# TaggerBits0_1.net
KiCad netlist of a schematic drawn in EAGLE
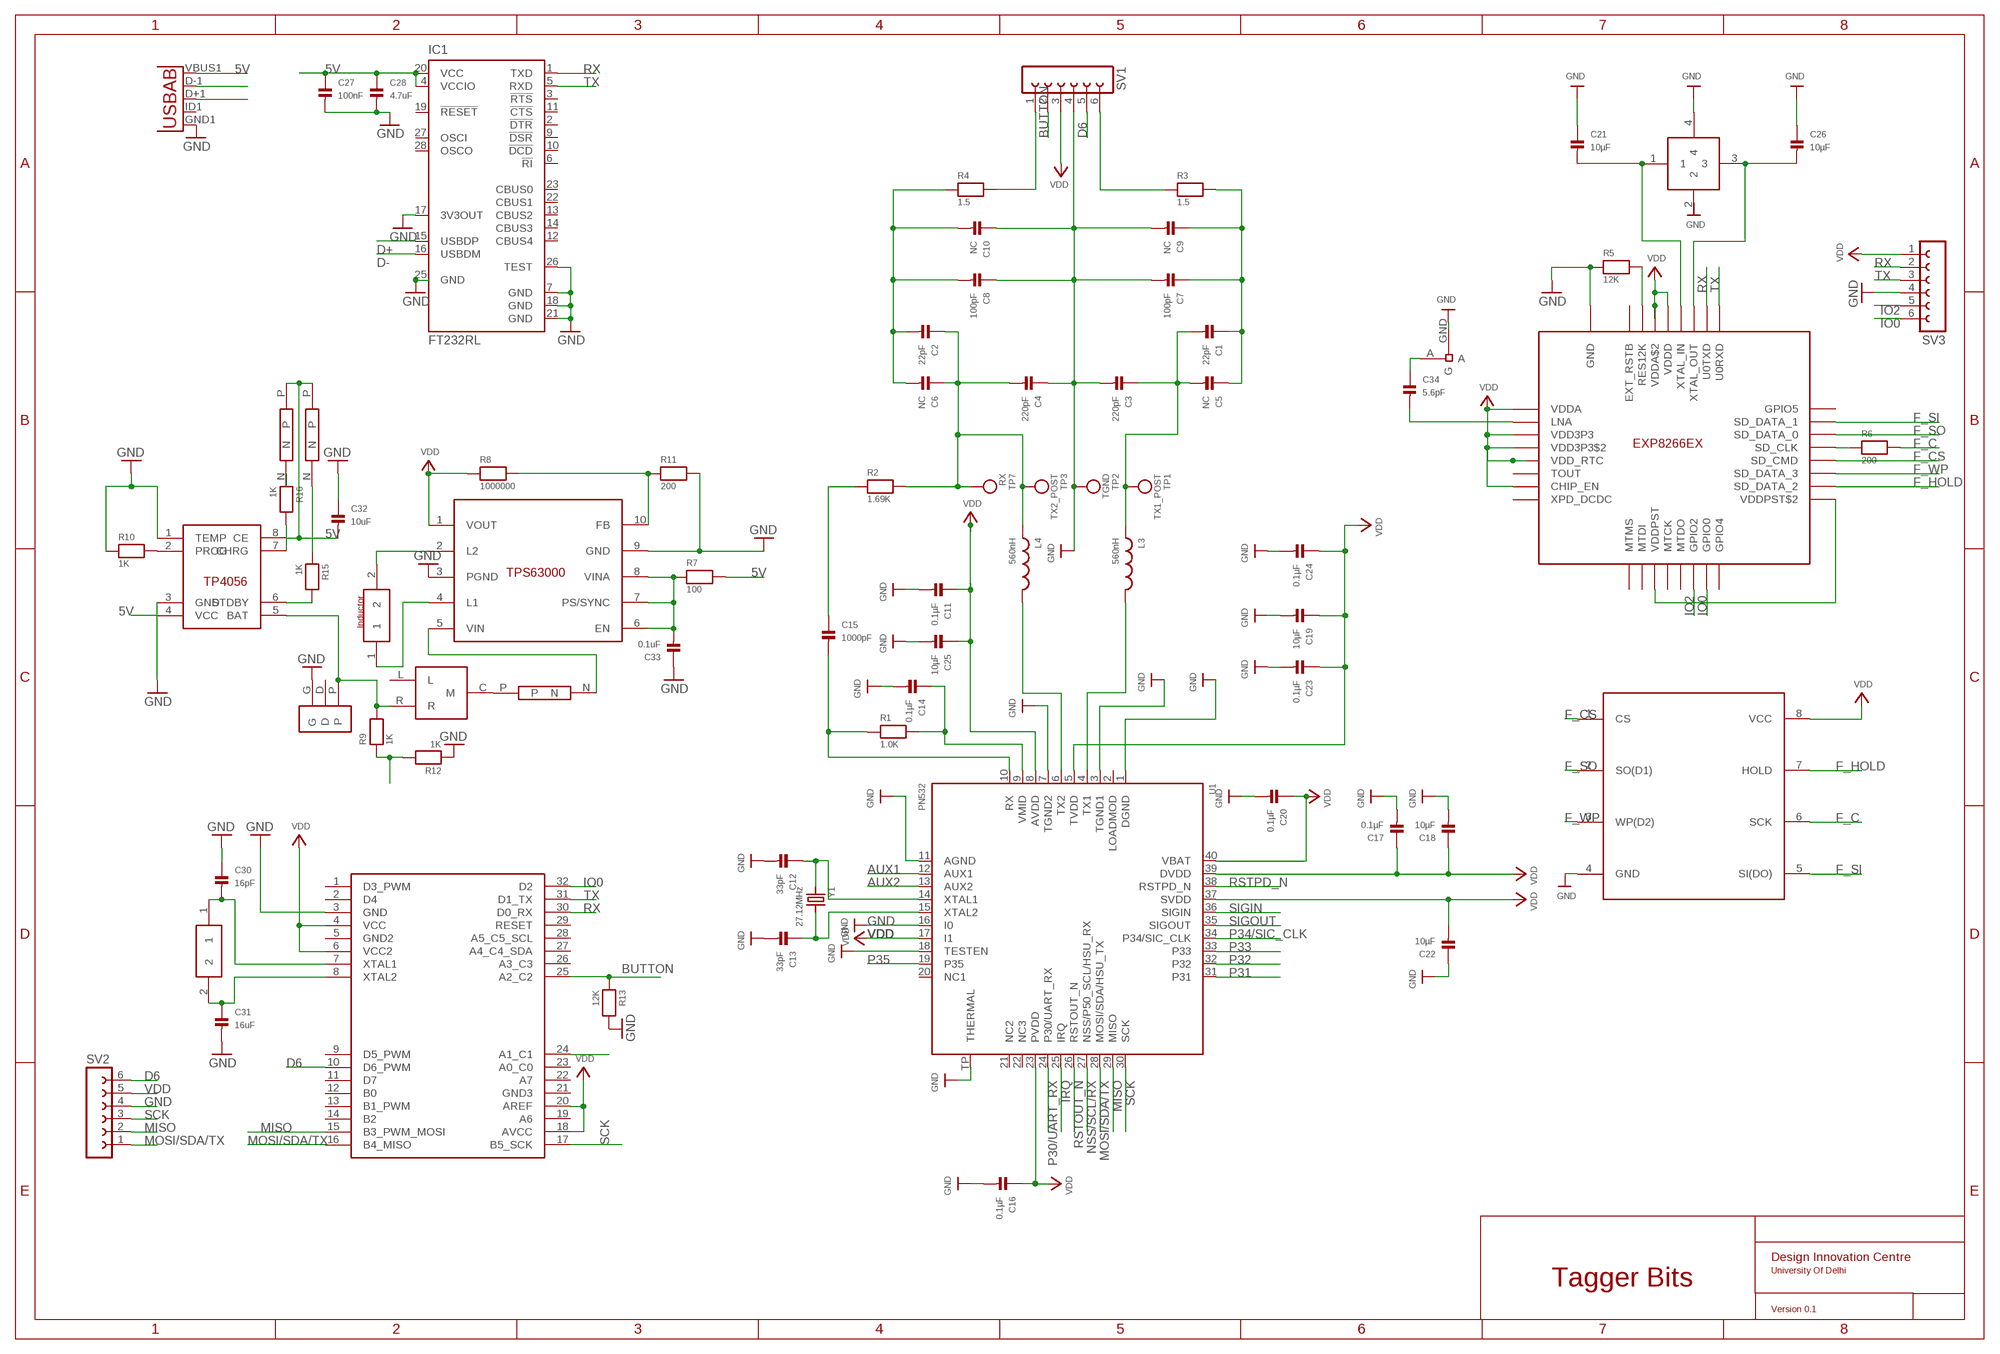
[diagram p0: schematic, sheet 1]

(export (version "E")
  (design (tool "Eeschema 10.0.6"))
  (components
    (comp (ref "C1")
      (value "22pF")
      (footprint "eagle-import:0805")
      (libsource (lib "eagle-import") (part "CAP_CERAMIC0805"))
    )
    (comp (ref "C2")
      (value "22pF")
      (footprint "eagle-import:0805")
      (libsource (lib "eagle-import") (part "CAP_CERAMIC0805"))
    )
    (comp (ref "C3")
      (value "220pF")
      (footprint "eagle-import:0805")
      (libsource (lib "eagle-import") (part "CAP_CERAMIC0805"))
    )
    (comp (ref "C4")
      (value "220pF")
      (footprint "eagle-import:0805")
      (libsource (lib "eagle-import") (part "CAP_CERAMIC0805"))
    )
    (comp (ref "C5")
      (value "NC")
      (footprint "eagle-import:0805")
      (libsource (lib "eagle-import") (part "CAP_CERAMIC0805"))
    )
    (comp (ref "C6")
      (value "NC")
      (footprint "eagle-import:0805")
      (libsource (lib "eagle-import") (part "CAP_CERAMIC0805"))
    )
    (comp (ref "C7")
      (value "100pF")
      (footprint "eagle-import:0805")
      (libsource (lib "eagle-import") (part "CAP_CERAMIC0805"))
    )
    (comp (ref "C8")
      (value "100pF")
      (footprint "eagle-import:0805")
      (libsource (lib "eagle-import") (part "CAP_CERAMIC0805"))
    )
    (comp (ref "C9")
      (value "NC")
      (footprint "eagle-import:0805")
      (libsource (lib "eagle-import") (part "CAP_CERAMIC0805"))
    )
    (comp (ref "C10")
      (value "NC")
      (footprint "eagle-import:0805")
      (libsource (lib "eagle-import") (part "CAP_CERAMIC0805"))
    )
    (comp (ref "C11")
      (value "0.1µF")
      (footprint "eagle-import:0805")
      (libsource (lib "eagle-import") (part "CAP_CERAMIC0805"))
    )
    (comp (ref "C12")
      (value "33pF")
      (footprint "eagle-import:0805")
      (libsource (lib "eagle-import") (part "CAP_CERAMIC0805"))
    )
    (comp (ref "C13")
      (value "33pF")
      (footprint "eagle-import:0805")
      (libsource (lib "eagle-import") (part "CAP_CERAMIC0805"))
    )
    (comp (ref "C14")
      (value "0.1µF")
      (footprint "eagle-import:0805")
      (libsource (lib "eagle-import") (part "CAP_CERAMIC0805"))
    )
    (comp (ref "C15")
      (value "1000pF")
      (footprint "eagle-import:0805")
      (libsource (lib "eagle-import") (part "CAP_CERAMIC0805"))
    )
    (comp (ref "C16")
      (value "0.1µF")
      (footprint "eagle-import:0805")
      (libsource (lib "eagle-import") (part "CAP_CERAMIC0805"))
    )
    (comp (ref "C17")
      (value "0.1µF")
      (footprint "eagle-import:0805")
      (libsource (lib "eagle-import") (part "CAP_CERAMIC0805"))
    )
    (comp (ref "C18")
      (value "10µF")
      (footprint "eagle-import:0805")
      (libsource (lib "eagle-import") (part "CAP_CERAMIC0805"))
    )
    (comp (ref "C19")
      (value "10µF")
      (footprint "eagle-import:0805")
      (libsource (lib "eagle-import") (part "CAP_CERAMIC0805"))
    )
    (comp (ref "C20")
      (value "0.1µF")
      (footprint "eagle-import:0805")
      (libsource (lib "eagle-import") (part "CAP_CERAMIC0805"))
    )
    (comp (ref "C21")
      (value "10µF")
      (footprint "eagle-import:0805")
      (libsource (lib "eagle-import") (part "CAP_CERAMIC0805"))
    )
    (comp (ref "C22")
      (value "10µF")
      (footprint "eagle-import:0805")
      (libsource (lib "eagle-import") (part "CAP_CERAMIC0805"))
    )
    (comp (ref "C23")
      (value "0.1µF")
      (footprint "eagle-import:0805")
      (libsource (lib "eagle-import") (part "CAP_CERAMIC0805"))
    )
    (comp (ref "C24")
      (value "0.1µF")
      (footprint "eagle-import:0805")
      (libsource (lib "eagle-import") (part "CAP_CERAMIC0805"))
    )
    (comp (ref "C25")
      (value "10µF")
      (footprint "eagle-import:0805")
      (libsource (lib "eagle-import") (part "CAP_CERAMIC0805"))
    )
    (comp (ref "C26")
      (value "10µF")
      (footprint "eagle-import:0805")
      (libsource (lib "eagle-import") (part "CAP_CERAMIC0805"))
    )
    (comp (ref "C27")
      (value "100nF")
      (footprint "eagle-import:0805")
      (libsource (lib "eagle-import") (part "CAP_CERAMIC0805"))
    )
    (comp (ref "C28")
      (value "4.7uF")
      (footprint "eagle-import:0805")
      (libsource (lib "eagle-import") (part "CAP_CERAMIC0805"))
    )
    (comp (ref "C30")
      (value "16pF")
      (footprint "eagle-import:0805")
      (libsource (lib "eagle-import") (part "CAP_CERAMIC0805"))
    )
    (comp (ref "C31")
      (value "16uF")
      (footprint "eagle-import:0805")
      (libsource (lib "eagle-import") (part "CAP_CERAMIC0805"))
    )
    (comp (ref "C32")
      (value "10uF")
      (footprint "eagle-import:0805")
      (libsource (lib "eagle-import") (part "CAP_CERAMIC0805"))
    )
    (comp (ref "C33")
      (value "0.1uF")
      (footprint "eagle-import:0805")
      (libsource (lib "eagle-import") (part "CAP_CERAMIC0805"))
    )
    (comp (ref "C34")
      (value "5.6pF")
      (footprint "eagle-import:0805")
      (libsource (lib "eagle-import") (part "CAP_CERAMIC0805"))
    )
    (comp (ref "GREEN")
      (value "LED(805)")
      (footprint "eagle-import:LED(805)")
      (libsource (lib "eagle-import") (part "LED(805)"))
    )
    (comp (ref "IC1")
      (value "FT232RL")
      (footprint "eagle-import:SSOP28")
      (libsource (lib "eagle-import") (part "FT232RL"))
    )
    (comp (ref "L3")
      (value "560nH")
      (footprint "eagle-import:0805")
      (libsource (lib "eagle-import") (part "INDUCTOR0805"))
    )
    (comp (ref "L4")
      (value "560nH")
      (footprint "eagle-import:0805")
      (libsource (lib "eagle-import") (part "INDUCTOR0805"))
    )
    (comp (ref "LED")
      (value "LED(805)")
      (footprint "eagle-import:LED(805)")
      (libsource (lib "eagle-import") (part "LED(805)"))
    )
    (comp (ref "R1")
      (value "1.0K")
      (footprint "eagle-import:0805")
      (libsource (lib "eagle-import") (part "RESISTOR0805"))
    )
    (comp (ref "R2")
      (value "1.69K")
      (footprint "eagle-import:0805")
      (libsource (lib "eagle-import") (part "RESISTOR0805"))
    )
    (comp (ref "R3")
      (value "1.5")
      (footprint "eagle-import:0805")
      (libsource (lib "eagle-import") (part "RESISTOR0805"))
    )
    (comp (ref "R4")
      (value "1.5")
      (footprint "eagle-import:0805")
      (libsource (lib "eagle-import") (part "RESISTOR0805"))
    )
    (comp (ref "R5")
      (value "12K")
      (footprint "eagle-import:0805")
      (libsource (lib "eagle-import") (part "RESISTOR0805"))
    )
    (comp (ref "R6")
      (value "200")
      (footprint "eagle-import:0805")
      (libsource (lib "eagle-import") (part "RESISTOR0805"))
    )
    (comp (ref "R7")
      (value "100")
      (footprint "eagle-import:0805")
      (libsource (lib "eagle-import") (part "RESISTOR0805"))
    )
    (comp (ref "R8")
      (value "1000000")
      (footprint "eagle-import:0805")
      (libsource (lib "eagle-import") (part "RESISTOR0805"))
    )
    (comp (ref "R9")
      (value "1K")
      (footprint "eagle-import:0805")
      (libsource (lib "eagle-import") (part "RESISTOR0805"))
    )
    (comp (ref "R10")
      (value "1K")
      (footprint "eagle-import:0805")
      (libsource (lib "eagle-import") (part "RESISTOR0805"))
    )
    (comp (ref "R11")
      (value "200")
      (footprint "eagle-import:0805")
      (libsource (lib "eagle-import") (part "RESISTOR0805"))
    )
    (comp (ref "R12")
      (value "1K")
      (footprint "eagle-import:0805")
      (libsource (lib "eagle-import") (part "RESISTOR0805"))
    )
    (comp (ref "R13")
      (value "12K")
      (footprint "eagle-import:0805")
      (libsource (lib "eagle-import") (part "RESISTOR0805"))
    )
    (comp (ref "R15")
      (value "1K")
      (footprint "eagle-import:0805")
      (libsource (lib "eagle-import") (part "RESISTOR0805"))
    )
    (comp (ref "R16")
      (value "1K")
      (footprint "eagle-import:0805")
      (libsource (lib "eagle-import") (part "RESISTOR0805"))
    )
    (comp (ref "RED")
      (value "LED(805)")
      (footprint "eagle-import:LED(805)")
      (libsource (lib "eagle-import") (part "LED(805)"))
    )
    (comp (ref "SV1")
      (value "FE06-1")
      (footprint "eagle-import:FE06")
      (libsource (lib "eagle-import") (part "FE06-1"))
    )
    (comp (ref "SV2")
      (value "FE06-1")
      (footprint "eagle-import:FE06")
      (libsource (lib "eagle-import") (part "FE06-1"))
    )
    (comp (ref "SV3")
      (value "FE06-1")
      (footprint "eagle-import:FE06")
      (libsource (lib "eagle-import") (part "FE06-1"))
    )
    (comp (ref "TP1")
      (value "TX1_POST")
      (footprint "eagle-import:TESTPOINT_PAD_2MM")
      (libsource (lib "eagle-import") (part "TESTPOINTPAD"))
    )
    (comp (ref "TP2")
      (value "TGND")
      (footprint "eagle-import:TESTPOINT_PAD_2MM")
      (libsource (lib "eagle-import") (part "TESTPOINTPAD"))
    )
    (comp (ref "TP3")
      (value "TX2_POST")
      (footprint "eagle-import:TESTPOINT_PAD_2MM")
      (libsource (lib "eagle-import") (part "TESTPOINTPAD"))
    )
    (comp (ref "TP7")
      (value "RX")
      (footprint "eagle-import:TESTPOINT_PAD_2MM")
      (libsource (lib "eagle-import") (part "TESTPOINTPAD"))
    )
    (comp (ref "U$3")
      (value "FLASH")
      (footprint "eagle-import:SO08")
      (libsource (lib "eagle-import") (part "FLASH"))
    )
    (comp (ref "U$6")
      (value "ATMEGA328TQFP")
      (footprint "eagle-import:TQFP32-08")
      (libsource (lib "eagle-import") (part "ATMEGA328TQFP"))
    )
    (comp (ref "U$31")
      (value "ANTENNAE")
      (footprint "eagle-import:ANTENNAE")
      (libsource (lib "eagle-import") (part "ANTENNAE"))
    )
    (comp (ref "U$33")
      (value "26MHZ")
      (footprint "eagle-import:T120")
      (libsource (lib "eagle-import") (part "26MHZ"))
    )
    (comp (ref "U$41")
      (value "TP4056")
      (footprint "eagle-import:SO08")
      (libsource (lib "eagle-import") (part "TP4056"))
    )
    (comp (ref "U$42")
      (value "CRYSTAL")
      (footprint "eagle-import:CRYSTAL")
      (libsource (lib "eagle-import") (part "CRYSTAL"))
    )
    (comp (ref "U$44")
      (value "TPS63000")
      (footprint "eagle-import:SON10")
      (libsource (lib "eagle-import") (part "TPS63000"))
    )
    (comp (ref "U$47")
      (value "SPDT")
      (footprint "eagle-import:SPDT")
      (libsource (lib "eagle-import") (part "SPDT"))
    )
    (comp (ref "U$48")
      (value "BCON")
      (footprint "eagle-import:BCON")
      (libsource (lib "eagle-import") (part "BCON"))
    )
    (comp (ref "U$49")
      (value "INDUCTOR")
      (footprint "eagle-import:INDUCTOR")
      (libsource (lib "eagle-import") (part "INDUCTOR"))
    )
    (comp (ref "U1")
      (value "PN532")
      (footprint "eagle-import:HVQFN40-6X6")
      (libsource (lib "eagle-import") (part "PN532"))
    )
    (comp (ref "U3")
      (value "USB\"\"")
      (footprint "eagle-import:USB-MICRO-SMD")
      (libsource (lib "eagle-import") (part "USB{dblquote}{dblquote}"))
    )
    (comp (ref "U4")
      (value "ESP8266EX")
      (footprint "eagle-import:ESP8266EX")
      (libsource (lib "eagle-import") (part "ESP8266EX"))
    )
    (comp (ref "Y1")
      (value "27.12MHz")
      (footprint "eagle-import:CRYSTAL_3.2X2.5")
      (libsource (lib "eagle-import") (part "CRYSTALTHIN"))
    )
  )
  (nets
    (net (code "1") (name "/5V") (class "Default")
      (node (ref "C27") (pin "1") (pinfunction "P$1_1") (pintype "passive"))
      (node (ref "C28") (pin "1") (pinfunction "P$1_1") (pintype "passive"))
      (node (ref "C32") (pin "2") (pinfunction "P$2_2") (pintype "passive"))
      (node (ref "GREEN") (pin "P") (pinfunction "P_P") (pintype "bidirectional"))
      (node (ref "IC1") (pin "20") (pinfunction "VCC_20") (pintype "power_in"))
      (node (ref "IC1") (pin "4") (pinfunction "VCCIO_4") (pintype "power_in"))
      (node (ref "R7") (pin "2") (pinfunction "2_2") (pintype "passive"))
      (node (ref "RED") (pin "P") (pinfunction "P_P") (pintype "bidirectional"))
      (node (ref "U$41") (pin "4") (pinfunction "VCC_4") (pintype "bidirectional"))
      (node (ref "U$41") (pin "8") (pinfunction "CE_8") (pintype "bidirectional"))
      (node (ref "U3") (pin "VBUS1") (pinfunction "VBUS_VBUS1") (pintype "bidirectional"))
    )
    (net (code "2") (name "/AUX1") (class "Default")
      (node (ref "U1") (pin "12") (pinfunction "AUX1_12") (pintype "bidirectional"))
    )
    (net (code "3") (name "/AUX2") (class "Default")
      (node (ref "U1") (pin "13") (pinfunction "AUX2_13") (pintype "bidirectional"))
    )
    (net (code "4") (name "/BATTERYI") (class "Default")
      (node (ref "R12") (pin "2") (pinfunction "2_2") (pintype "passive"))
      (node (ref "R9") (pin "1") (pinfunction "1_1") (pintype "passive"))
      (node (ref "U$6") (pin "24") (pinfunction "A1_C1_24") (pintype "bidirectional"))
    )
    (net (code "5") (name "/BUTTON") (class "Default")
      (node (ref "R13") (pin "1") (pinfunction "1_1") (pintype "passive"))
      (node (ref "SV1") (pin "2") (pinfunction "2_2") (pintype "passive"))
      (node (ref "U$6") (pin "25") (pinfunction "A2_C2_25") (pintype "bidirectional"))
    )
    (net (code "6") (name "/D+") (class "Default")
      (node (ref "IC1") (pin "15") (pinfunction "USBDP_15") (pintype "bidirectional"))
      (node (ref "U3") (pin "D+1") (pinfunction "D+_D+1") (pintype "bidirectional"))
    )
    (net (code "7") (name "/D-") (class "Default")
      (node (ref "IC1") (pin "16") (pinfunction "USBDM_16") (pintype "bidirectional"))
      (node (ref "U3") (pin "D-1") (pinfunction "D-_D-1") (pintype "bidirectional"))
    )
    (net (code "8") (name "/D6") (class "Default")
      (node (ref "SV1") (pin "5") (pinfunction "5_5") (pintype "passive"))
      (node (ref "SV2") (pin "6") (pinfunction "6_6") (pintype "passive"))
      (node (ref "U$6") (pin "10") (pinfunction "D6_PWM_10") (pintype "bidirectional"))
    )
    (net (code "9") (name "/F_C") (class "Default")
      (node (ref "R6") (pin "2") (pinfunction "2_2") (pintype "passive"))
      (node (ref "U$3") (pin "6") (pinfunction "SCK_6") (pintype "bidirectional"))
    )
    (net (code "10") (name "/F_CS") (class "Default")
      (node (ref "U$3") (pin "1") (pinfunction "CS_1") (pintype "bidirectional"))
      (node (ref "U4") (pin "SD_CMD") (pinfunction "SD_CMD_SD_CMD") (pintype "bidirectional"))
    )
    (net (code "11") (name "/F_HOLD") (class "Default")
      (node (ref "U$3") (pin "7") (pinfunction "HOLD_7") (pintype "bidirectional"))
      (node (ref "U4") (pin "SD_DATA_2") (pinfunction "SD_DATA_2_SD_DATA_2") (pintype "bidirectional"))
    )
    (net (code "12") (name "/F_SI") (class "Default")
      (node (ref "U$3") (pin "5") (pinfunction "SI(DO)_5") (pintype "bidirectional"))
      (node (ref "U4") (pin "SD_DATA_1") (pinfunction "SD_DATA_1_SD_DATA_1") (pintype "bidirectional"))
    )
    (net (code "13") (name "/F_SO") (class "Default")
      (node (ref "U$3") (pin "2") (pinfunction "SO(D1)_2") (pintype "bidirectional"))
      (node (ref "U4") (pin "SD_DATA_0") (pinfunction "SD_DATA_0_SD_DATA_0") (pintype "bidirectional"))
    )
    (net (code "14") (name "/F_WP") (class "Default")
      (node (ref "U$3") (pin "3") (pinfunction "WP(D2)_3") (pintype "bidirectional"))
      (node (ref "U4") (pin "SD_DATA_3") (pinfunction "SD_DATA_3_SD_DATA_3") (pintype "bidirectional"))
    )
    (net (code "15") (name "/IO0") (class "Default")
      (node (ref "SV3") (pin "6") (pinfunction "6_6") (pintype "passive"))
      (node (ref "U$6") (pin "32") (pinfunction "D2_32") (pintype "bidirectional"))
      (node (ref "U4") (pin "GPIO0") (pinfunction "GPIO0_GPIO0") (pintype "bidirectional"))
    )
    (net (code "16") (name "/IO2") (class "Default")
      (node (ref "SV3") (pin "5") (pinfunction "5_5") (pintype "passive"))
      (node (ref "U4") (pin "GPIO2") (pinfunction "GPIO2_GPIO2") (pintype "bidirectional"))
    )
    (net (code "17") (name "/IRQ") (class "Default")
      (node (ref "U1") (pin "25") (pinfunction "IRQ_25") (pintype "bidirectional"))
    )
    (net (code "18") (name "/MISO") (class "Default")
      (node (ref "SV2") (pin "2") (pinfunction "2_2") (pintype "passive"))
      (node (ref "U$6") (pin "15") (pinfunction "B3_PWM_MOSI_15") (pintype "bidirectional"))
      (node (ref "U1") (pin "29") (pinfunction "MISO_29") (pintype "bidirectional"))
    )
    (net (code "19") (name "/MOSI{slash}SDA{slash}TX") (class "Default")
      (node (ref "SV2") (pin "1") (pinfunction "1_1") (pintype "passive"))
      (node (ref "U$6") (pin "16") (pinfunction "B4_MISO_16") (pintype "bidirectional"))
      (node (ref "U1") (pin "28") (pinfunction "MOSI/SDA/HSU_TX_28") (pintype "bidirectional"))
    )
    (net (code "20") (name "/NSS{slash}SCL{slash}RX") (class "Default")
      (node (ref "U1") (pin "27") (pinfunction "NSS/P50_SCL/HSU_RX_27") (pintype "bidirectional"))
    )
    (net (code "21") (name "/P30{slash}UART_RX") (class "Default")
      (node (ref "U1") (pin "24") (pinfunction "P30/UART_RX_24") (pintype "bidirectional"))
    )
    (net (code "22") (name "/P31") (class "Default")
      (node (ref "U1") (pin "31") (pinfunction "P31_31") (pintype "bidirectional"))
    )
    (net (code "23") (name "/P32") (class "Default")
      (node (ref "U1") (pin "32") (pinfunction "P32_32") (pintype "bidirectional"))
    )
    (net (code "24") (name "/P33") (class "Default")
      (node (ref "U1") (pin "33") (pinfunction "P33_33") (pintype "bidirectional"))
    )
    (net (code "25") (name "/P34{slash}SIC_CLK") (class "Default")
      (node (ref "U1") (pin "34") (pinfunction "P34/SIC_CLK_34") (pintype "bidirectional"))
    )
    (net (code "26") (name "/P35") (class "Default")
      (node (ref "U1") (pin "19") (pinfunction "P35_19") (pintype "bidirectional"))
    )
    (net (code "27") (name "/RSTOUT_N") (class "Default")
      (node (ref "U1") (pin "26") (pinfunction "RSTOUT_N_26") (pintype "bidirectional"))
    )
    (net (code "28") (name "/RSTPD_N") (class "Default")
      (node (ref "U1") (pin "38") (pinfunction "RSTPD_N_38") (pintype "bidirectional"))
    )
    (net (code "29") (name "/RX") (class "Default")
      (node (ref "IC1") (pin "1") (pinfunction "TXD_1") (pintype "output"))
      (node (ref "SV3") (pin "2") (pinfunction "2_2") (pintype "passive"))
      (node (ref "U$6") (pin "30") (pinfunction "D0_RX_30") (pintype "bidirectional"))
      (node (ref "U4") (pin "U0TXD") (pinfunction "U0TXD_U0TXD") (pintype "bidirectional"))
    )
    (net (code "30") (name "/SCK") (class "Default")
      (node (ref "SV2") (pin "3") (pinfunction "3_3") (pintype "passive"))
      (node (ref "U$6") (pin "17") (pinfunction "B5_SCK_17") (pintype "bidirectional"))
      (node (ref "U1") (pin "30") (pinfunction "SCK_30") (pintype "bidirectional"))
    )
    (net (code "31") (name "/SIGIN") (class "Default")
      (node (ref "U1") (pin "36") (pinfunction "SIGIN_36") (pintype "bidirectional"))
    )
    (net (code "32") (name "/SIGOUT") (class "Default")
      (node (ref "U1") (pin "35") (pinfunction "SIGOUT_35") (pintype "bidirectional"))
    )
    (net (code "33") (name "/TX") (class "Default")
      (node (ref "IC1") (pin "5") (pinfunction "RXD_5") (pintype "input"))
      (node (ref "SV3") (pin "3") (pinfunction "3_3") (pintype "passive"))
      (node (ref "U$6") (pin "31") (pinfunction "D1_TX_31") (pintype "bidirectional"))
      (node (ref "U4") (pin "U0RXD") (pinfunction "U0RXD_U0RXD") (pintype "bidirectional"))
    )
    (net (code "34") (name "GND") (class "Default")
      (node (ref "C10") (pin "1") (pinfunction "P$1_1") (pintype "passive"))
      (node (ref "C11") (pin "2") (pinfunction "P$2_2") (pintype "passive"))
      (node (ref "C12") (pin "2") (pinfunction "P$2_2") (pintype "passive"))
      (node (ref "C13") (pin "2") (pinfunction "P$2_2") (pintype "passive"))
      (node (ref "C14") (pin "2") (pinfunction "P$2_2") (pintype "passive"))
      (node (ref "C16") (pin "2") (pinfunction "P$2_2") (pintype "passive"))
      (node (ref "C17") (pin "2") (pinfunction "P$2_2") (pintype "passive"))
      (node (ref "C18") (pin "2") (pinfunction "P$2_2") (pintype "passive"))
      (node (ref "C19") (pin "2") (pinfunction "P$2_2") (pintype "passive"))
      (node (ref "C20") (pin "2") (pinfunction "P$2_2") (pintype "passive"))
      (node (ref "C21") (pin "1") (pinfunction "P$1_1") (pintype "passive"))
      (node (ref "C22") (pin "1") (pinfunction "P$1_1") (pintype "passive"))
      (node (ref "C23") (pin "2") (pinfunction "P$2_2") (pintype "passive"))
      (node (ref "C24") (pin "2") (pinfunction "P$2_2") (pintype "passive"))
      (node (ref "C25") (pin "2") (pinfunction "P$2_2") (pintype "passive"))
      (node (ref "C26") (pin "1") (pinfunction "P$1_1") (pintype "passive"))
      (node (ref "C27") (pin "2") (pinfunction "P$2_2") (pintype "passive"))
      (node (ref "C28") (pin "2") (pinfunction "P$2_2") (pintype "passive"))
      (node (ref "C3") (pin "2") (pinfunction "P$2_2") (pintype "passive"))
      (node (ref "C30") (pin "1") (pinfunction "P$1_1") (pintype "passive"))
      (node (ref "C31") (pin "2") (pinfunction "P$2_2") (pintype "passive"))
      (node (ref "C32") (pin "1") (pinfunction "P$1_1") (pintype "passive"))
      (node (ref "C33") (pin "1") (pinfunction "P$1_1") (pintype "passive"))
      (node (ref "C4") (pin "1") (pinfunction "P$1_1") (pintype "passive"))
      (node (ref "C7") (pin "2") (pinfunction "P$2_2") (pintype "passive"))
      (node (ref "C8") (pin "1") (pinfunction "P$1_1") (pintype "passive"))
      (node (ref "C9") (pin "2") (pinfunction "P$2_2") (pintype "passive"))
      (node (ref "IC1") (pin "17") (pinfunction "3V3OUT_17") (pintype "output"))
      (node (ref "IC1") (pin "18") (pinfunction "GND_18") (pintype "power_in"))
      (node (ref "IC1") (pin "21") (pinfunction "GND_21") (pintype "power_in"))
      (node (ref "IC1") (pin "25") (pinfunction "GND_25") (pintype "power_in"))
      (node (ref "IC1") (pin "26") (pinfunction "TEST_26") (pintype "input"))
      (node (ref "IC1") (pin "7") (pinfunction "GND_7") (pintype "power_in"))
      (node (ref "R10") (pin "1") (pinfunction "1_1") (pintype "passive"))
      (node (ref "R11") (pin "2") (pinfunction "2_2") (pintype "passive"))
      (node (ref "R12") (pin "1") (pinfunction "1_1") (pintype "passive"))
      (node (ref "R13") (pin "2") (pinfunction "2_2") (pintype "passive"))
      (node (ref "R5") (pin "1") (pinfunction "1_1") (pintype "passive"))
      (node (ref "SV1") (pin "4") (pinfunction "4_4") (pintype "passive"))
      (node (ref "SV2") (pin "4") (pinfunction "4_4") (pintype "passive"))
      (node (ref "SV3") (pin "4") (pinfunction "4_4") (pintype "passive"))
      (node (ref "TP2") (pin "P$1") (pinfunction "P$1_P$1") (pintype "bidirectional"))
      (node (ref "U$3") (pin "4") (pinfunction "GND_4") (pintype "bidirectional"))
      (node (ref "U$31") (pin "GND") (pinfunction "G_GND") (pintype "bidirectional"))
      (node (ref "U$33") (pin "4") (pinfunction "4_4") (pintype "bidirectional"))
      (node (ref "U$41") (pin "1") (pinfunction "TEMP_1") (pintype "bidirectional"))
      (node (ref "U$41") (pin "3") (pinfunction "GND_3") (pintype "bidirectional"))
      (node (ref "U$44") (pin "3") (pinfunction "PGND_3") (pintype "bidirectional"))
      (node (ref "U$44") (pin "9") (pinfunction "GND_9") (pintype "bidirectional"))
      (node (ref "U$48") (pin "G") (pinfunction "G_G") (pintype "bidirectional"))
      (node (ref "U$6") (pin "3") (pinfunction "GND_3") (pintype "bidirectional"))
      (node (ref "U1") (pin "1") (pinfunction "DGND_1") (pintype "bidirectional"))
      (node (ref "U1") (pin "11") (pinfunction "AGND_11") (pintype "bidirectional"))
      (node (ref "U1") (pin "16") (pinfunction "I0_16") (pintype "bidirectional"))
      (node (ref "U1") (pin "18") (pinfunction "TESTEN_18") (pintype "bidirectional"))
      (node (ref "U1") (pin "3") (pinfunction "TGND1_3") (pintype "bidirectional"))
      (node (ref "U1") (pin "7") (pinfunction "TGND2_7") (pintype "bidirectional"))
      (node (ref "U1") (pin "TP") (pinfunction "THERMAL_TP") (pintype "bidirectional"))
      (node (ref "U3") (pin "GND1") (pinfunction "GND_GND1") (pintype "bidirectional"))
      (node (ref "U4") (pin "GND") (pinfunction "GND_GND") (pintype "bidirectional"))
    )
    (net (code "35") (name "Net-(C1-P$1)") (class "Default")
      (node (ref "C1") (pin "1") (pinfunction "P$1_1") (pintype "passive"))
      (node (ref "C5") (pin "1") (pinfunction "P$1_1") (pintype "passive"))
      (node (ref "C7") (pin "1") (pinfunction "P$1_1") (pintype "passive"))
      (node (ref "C9") (pin "1") (pinfunction "P$1_1") (pintype "passive"))
      (node (ref "R3") (pin "2") (pinfunction "2_2") (pintype "passive"))
    )
    (net (code "36") (name "Net-(C1-P$2)") (class "Default")
      (node (ref "C1") (pin "2") (pinfunction "P$2_2") (pintype "passive"))
      (node (ref "C3") (pin "1") (pinfunction "P$1_1") (pintype "passive"))
      (node (ref "C5") (pin "2") (pinfunction "P$2_2") (pintype "passive"))
      (node (ref "L3") (pin "1") (pinfunction "1_1") (pintype "passive"))
      (node (ref "TP1") (pin "P$1") (pinfunction "P$1_P$1") (pintype "bidirectional"))
    )
    (net (code "37") (name "Net-(C2-P$1)") (class "Default")
      (node (ref "C2") (pin "1") (pinfunction "P$1_1") (pintype "passive"))
      (node (ref "C4") (pin "2") (pinfunction "P$2_2") (pintype "passive"))
      (node (ref "C6") (pin "1") (pinfunction "P$1_1") (pintype "passive"))
      (node (ref "L4") (pin "1") (pinfunction "1_1") (pintype "passive"))
      (node (ref "R2") (pin "2") (pinfunction "2_2") (pintype "passive"))
      (node (ref "TP3") (pin "P$1") (pinfunction "P$1_P$1") (pintype "bidirectional"))
      (node (ref "TP7") (pin "P$1") (pinfunction "P$1_P$1") (pintype "bidirectional"))
    )
    (net (code "38") (name "Net-(C10-P$2)") (class "Default")
      (node (ref "C10") (pin "2") (pinfunction "P$2_2") (pintype "passive"))
      (node (ref "C2") (pin "2") (pinfunction "P$2_2") (pintype "passive"))
      (node (ref "C6") (pin "2") (pinfunction "P$2_2") (pintype "passive"))
      (node (ref "C8") (pin "2") (pinfunction "P$2_2") (pintype "passive"))
      (node (ref "R4") (pin "1") (pinfunction "1_1") (pintype "passive"))
    )
    (net (code "39") (name "Net-(C12-P$1)") (class "Default")
      (node (ref "C12") (pin "1") (pinfunction "P$1_1") (pintype "passive"))
      (node (ref "U1") (pin "14") (pinfunction "XTAL1_14") (pintype "bidirectional"))
      (node (ref "Y1") (pin "1") (pinfunction "1_1") (pintype "passive"))
    )
    (net (code "40") (name "Net-(C13-P$1)") (class "Default")
      (node (ref "C13") (pin "1") (pinfunction "P$1_1") (pintype "passive"))
      (node (ref "U1") (pin "15") (pinfunction "XTAL2_15") (pintype "bidirectional"))
      (node (ref "Y1") (pin "2") (pinfunction "2_2") (pintype "passive"))
    )
    (net (code "41") (name "Net-(C14-P$1)") (class "Default")
      (node (ref "C14") (pin "1") (pinfunction "P$1_1") (pintype "passive"))
      (node (ref "R1") (pin "2") (pinfunction "2_2") (pintype "passive"))
      (node (ref "U1") (pin "9") (pinfunction "VMID_9") (pintype "bidirectional"))
    )
    (net (code "42") (name "Net-(C15-P$1)") (class "Default")
      (node (ref "C15") (pin "1") (pinfunction "P$1_1") (pintype "passive"))
      (node (ref "R2") (pin "1") (pinfunction "1_1") (pintype "passive"))
    )
    (net (code "43") (name "Net-(C15-P$2)") (class "Default")
      (node (ref "C15") (pin "2") (pinfunction "P$2_2") (pintype "passive"))
      (node (ref "R1") (pin "1") (pinfunction "1_1") (pintype "passive"))
      (node (ref "U1") (pin "10") (pinfunction "RX_10") (pintype "bidirectional"))
    )
    (net (code "44") (name "Net-(C21-P$2)") (class "Default")
      (node (ref "C21") (pin "2") (pinfunction "P$2_2") (pintype "passive"))
      (node (ref "U$33") (pin "1") (pinfunction "1_1") (pintype "bidirectional"))
      (node (ref "U4") (pin "XTAL_IN") (pinfunction "XTAL_IN_XTAL_IN") (pintype "bidirectional"))
    )
    (net (code "45") (name "Net-(C26-P$2)") (class "Default")
      (node (ref "C26") (pin "2") (pinfunction "P$2_2") (pintype "passive"))
      (node (ref "U$33") (pin "3") (pinfunction "3_3") (pintype "bidirectional"))
      (node (ref "U4") (pin "XTAL_OUT") (pinfunction "XTAL_OUT_XTAL_OUT") (pintype "bidirectional"))
    )
    (net (code "46") (name "Net-(C30-P$2)") (class "Default")
      (node (ref "C30") (pin "2") (pinfunction "P$2_2") (pintype "passive"))
      (node (ref "U$42") (pin "1") (pinfunction "1_1") (pintype "bidirectional"))
      (node (ref "U$6") (pin "7") (pinfunction "XTAL1_7") (pintype "bidirectional"))
    )
    (net (code "47") (name "Net-(C31-P$1)") (class "Default")
      (node (ref "C31") (pin "1") (pinfunction "P$1_1") (pintype "passive"))
      (node (ref "U$42") (pin "2") (pinfunction "2_2") (pintype "bidirectional"))
      (node (ref "U$6") (pin "8") (pinfunction "XTAL2_8") (pintype "bidirectional"))
    )
    (net (code "48") (name "Net-(C33-P$2)") (class "Default")
      (node (ref "C33") (pin "2") (pinfunction "P$2_2") (pintype "passive"))
      (node (ref "R7") (pin "1") (pinfunction "1_1") (pintype "passive"))
      (node (ref "U$44") (pin "6") (pinfunction "EN_6") (pintype "bidirectional"))
      (node (ref "U$44") (pin "7") (pinfunction "PS/SYNC_7") (pintype "bidirectional"))
      (node (ref "U$44") (pin "8") (pinfunction "VINA_8") (pintype "bidirectional"))
    )
    (net (code "49") (name "Net-(C34-P$1)") (class "Default")
      (node (ref "C34") (pin "1") (pinfunction "P$1_1") (pintype "passive"))
      (node (ref "U$31") (pin "A") (pinfunction "A_A") (pintype "bidirectional"))
    )
    (net (code "50") (name "Net-(C34-P$2)") (class "Default")
      (node (ref "C34") (pin "2") (pinfunction "P$2_2") (pintype "passive"))
      (node (ref "U4") (pin "LNA") (pinfunction "LNA_LNA") (pintype "bidirectional"))
    )
    (net (code "51") (name "Net-(GREEN-PadN)") (class "Default")
      (node (ref "GREEN") (pin "N") (pinfunction "N_N") (pintype "bidirectional"))
      (node (ref "R15") (pin "1") (pinfunction "1_1") (pintype "passive"))
    )
    (net (code "52") (name "Net-(R3-Pad1)") (class "Default")
      (node (ref "R3") (pin "1") (pinfunction "1_1") (pintype "passive"))
      (node (ref "SV1") (pin "6") (pinfunction "6_6") (pintype "passive"))
    )
    (net (code "53") (name "Net-(R4-Pad2)") (class "Default")
      (node (ref "R4") (pin "2") (pinfunction "2_2") (pintype "passive"))
      (node (ref "SV1") (pin "1") (pinfunction "1_1") (pintype "passive"))
    )
    (net (code "54") (name "Net-(R5-Pad2)") (class "Default")
      (node (ref "R5") (pin "2") (pinfunction "2_2") (pintype "passive"))
      (node (ref "U4") (pin "RES12K") (pinfunction "RES12K_RES12K") (pintype "bidirectional"))
    )
    (net (code "55") (name "Net-(R6-Pad1)") (class "Default")
      (node (ref "R6") (pin "1") (pinfunction "1_1") (pintype "passive"))
      (node (ref "U4") (pin "SD_CLK") (pinfunction "SD_CLK_SD_CLK") (pintype "bidirectional"))
    )
    (net (code "56") (name "Net-(R16-Pad1)") (class "Default")
      (node (ref "R16") (pin "1") (pinfunction "1_1") (pintype "passive"))
      (node (ref "RED") (pin "N") (pinfunction "N_N") (pintype "bidirectional"))
    )
    (net (code "57") (name "Net-(U$41-BAT)") (class "Default")
      (node (ref "R9") (pin "2") (pinfunction "2_2") (pintype "passive"))
      (node (ref "U$41") (pin "5") (pinfunction "BAT_5") (pintype "bidirectional"))
      (node (ref "U$47") (pin "R") (pinfunction "R_R") (pintype "bidirectional"))
      (node (ref "U$48") (pin "P") (pinfunction "P_P") (pintype "bidirectional"))
    )
    (net (code "58") (name "Net-(U$41-CHRG)") (class "Default")
      (node (ref "R16") (pin "2") (pinfunction "2_2") (pintype "passive"))
      (node (ref "U$41") (pin "7") (pinfunction "CHRG_7") (pintype "bidirectional"))
    )
    (net (code "59") (name "Net-(U$41-PROG)") (class "Default")
      (node (ref "R10") (pin "2") (pinfunction "2_2") (pintype "passive"))
      (node (ref "U$41") (pin "2") (pinfunction "PROG_2") (pintype "bidirectional"))
    )
    (net (code "60") (name "Net-(U$41-STDBY)") (class "Default")
      (node (ref "R15") (pin "2") (pinfunction "2_2") (pintype "passive"))
      (node (ref "U$41") (pin "6") (pinfunction "STDBY_6") (pintype "bidirectional"))
    )
    (net (code "61") (name "Net-(U$44-FB)") (class "Default")
      (node (ref "R11") (pin "1") (pinfunction "1_1") (pintype "passive"))
      (node (ref "R8") (pin "2") (pinfunction "2_2") (pintype "passive"))
      (node (ref "U$44") (pin "10") (pinfunction "FB_10") (pintype "bidirectional"))
    )
    (net (code "62") (name "Net-(U$44-L1)") (class "Default")
      (node (ref "U$44") (pin "4") (pinfunction "L1_4") (pintype "bidirectional"))
      (node (ref "U$49") (pin "1") (pinfunction "1_1") (pintype "bidirectional"))
    )
    (net (code "63") (name "Net-(U$44-L2)") (class "Default")
      (node (ref "U$44") (pin "2") (pinfunction "L2_2") (pintype "bidirectional"))
      (node (ref "U$49") (pin "2") (pinfunction "2_2") (pintype "bidirectional"))
    )
    (net (code "64") (name "Net-(U$44-VIN)") (class "Default")
      (node (ref "LED") (pin "N") (pinfunction "N_N") (pintype "bidirectional"))
      (node (ref "U$44") (pin "5") (pinfunction "VIN_5") (pintype "bidirectional"))
    )
    (net (code "65") (name "Net-(U$47-M)") (class "Default")
      (node (ref "LED") (pin "P") (pinfunction "P_P") (pintype "bidirectional"))
      (node (ref "U$47") (pin "C") (pinfunction "M_C") (pintype "bidirectional"))
    )
    (net (code "66") (name "Net-(U1-TX1)") (class "Default")
      (node (ref "L3") (pin "2") (pinfunction "2_2") (pintype "passive"))
      (node (ref "U1") (pin "4") (pinfunction "TX1_4") (pintype "bidirectional"))
    )
    (net (code "67") (name "Net-(U1-TX2)") (class "Default")
      (node (ref "L4") (pin "2") (pinfunction "2_2") (pintype "passive"))
      (node (ref "U1") (pin "6") (pinfunction "TX2_6") (pintype "bidirectional"))
    )
    (net (code "68") (name "Net-(U4-PadVDDPST$2)") (class "Default")
      (node (ref "U4") (pin "VDDPST") (pinfunction "VDDPST_VDDPST") (pintype "bidirectional"))
      (node (ref "U4") (pin "VDDPST$2") (pinfunction "VDDPST$2_VDDPST$2") (pintype "bidirectional"))
    )
    (net (code "69") (name "VDD") (class "Default")
      (node (ref "C11") (pin "1") (pinfunction "P$1_1") (pintype "passive"))
      (node (ref "C16") (pin "1") (pinfunction "P$1_1") (pintype "passive"))
      (node (ref "C17") (pin "1") (pinfunction "P$1_1") (pintype "passive"))
      (node (ref "C18") (pin "1") (pinfunction "P$1_1") (pintype "passive"))
      (node (ref "C19") (pin "1") (pinfunction "P$1_1") (pintype "passive"))
      (node (ref "C20") (pin "1") (pinfunction "P$1_1") (pintype "passive"))
      (node (ref "C22") (pin "2") (pinfunction "P$2_2") (pintype "passive"))
      (node (ref "C23") (pin "1") (pinfunction "P$1_1") (pintype "passive"))
      (node (ref "C24") (pin "1") (pinfunction "P$1_1") (pintype "passive"))
      (node (ref "C25") (pin "1") (pinfunction "P$1_1") (pintype "passive"))
      (node (ref "R8") (pin "1") (pinfunction "1_1") (pintype "passive"))
      (node (ref "SV1") (pin "3") (pinfunction "3_3") (pintype "passive"))
      (node (ref "SV2") (pin "5") (pinfunction "5_5") (pintype "passive"))
      (node (ref "SV3") (pin "1") (pinfunction "1_1") (pintype "passive"))
      (node (ref "U$3") (pin "8") (pinfunction "VCC_8") (pintype "bidirectional"))
      (node (ref "U$44") (pin "1") (pinfunction "VOUT_1") (pintype "bidirectional"))
      (node (ref "U$6") (pin "18") (pinfunction "AVCC_18") (pintype "bidirectional"))
      (node (ref "U$6") (pin "20") (pinfunction "AREF_20") (pintype "bidirectional"))
      (node (ref "U$6") (pin "4") (pinfunction "VCC_4") (pintype "bidirectional"))
      (node (ref "U$6") (pin "6") (pinfunction "VCC2_6") (pintype "bidirectional"))
      (node (ref "U1") (pin "17") (pinfunction "I1_17") (pintype "bidirectional"))
      (node (ref "U1") (pin "23") (pinfunction "PVDD_23") (pintype "bidirectional"))
      (node (ref "U1") (pin "37") (pinfunction "SVDD_37") (pintype "bidirectional"))
      (node (ref "U1") (pin "39") (pinfunction "DVDD_39") (pintype "bidirectional"))
      (node (ref "U1") (pin "40") (pinfunction "VBAT_40") (pintype "bidirectional"))
      (node (ref "U1") (pin "5") (pinfunction "TVDD_5") (pintype "bidirectional"))
      (node (ref "U1") (pin "8") (pinfunction "AVDD_8") (pintype "bidirectional"))
      (node (ref "U4") (pin "CHIP_EN") (pinfunction "CHIP_EN_CHIP_EN") (pintype "bidirectional"))
      (node (ref "U4") (pin "VDD3P3") (pinfunction "VDD3P3_VDD3P3") (pintype "bidirectional"))
      (node (ref "U4") (pin "VDD3P3$2") (pinfunction "VDD3P3$2_VDD3P3$2") (pintype "bidirectional"))
      (node (ref "U4") (pin "VDDA") (pinfunction "VDDA_VDDA") (pintype "bidirectional"))
      (node (ref "U4") (pin "VDDA$2") (pinfunction "VDDA$2_VDDA$2") (pintype "bidirectional"))
      (node (ref "U4") (pin "VDDD") (pinfunction "VDDD_VDDD") (pintype "bidirectional"))
      (node (ref "U4") (pin "VDD_RTC") (pinfunction "VDD_RTC_VDD_RTC") (pintype "bidirectional"))
    )
    (net (code "70") (name "unconnected-(IC1-CBUS0-Pad23)") (class "Default")
      (node (ref "IC1") (pin "23") (pinfunction "CBUS0_23") (pintype "bidirectional"))
    )
    (net (code "71") (name "unconnected-(IC1-CBUS1-Pad22)") (class "Default")
      (node (ref "IC1") (pin "22") (pinfunction "CBUS1_22") (pintype "bidirectional"))
    )
    (net (code "72") (name "unconnected-(IC1-CBUS2-Pad13)") (class "Default")
      (node (ref "IC1") (pin "13") (pinfunction "CBUS2_13") (pintype "bidirectional"))
    )
    (net (code "73") (name "unconnected-(IC1-CBUS3-Pad14)") (class "Default")
      (node (ref "IC1") (pin "14") (pinfunction "CBUS3_14") (pintype "bidirectional"))
    )
    (net (code "74") (name "unconnected-(IC1-CBUS4-Pad12)") (class "Default")
      (node (ref "IC1") (pin "12") (pinfunction "CBUS4_12") (pintype "bidirectional"))
    )
    (net (code "75") (name "unconnected-(IC1-OSCI-Pad27)") (class "Default")
      (node (ref "IC1") (pin "27") (pinfunction "OSCI_27") (pintype "input"))
    )
    (net (code "76") (name "unconnected-(IC1-OSCO-Pad28)") (class "Default")
      (node (ref "IC1") (pin "28") (pinfunction "OSCO_28") (pintype "output"))
    )
    (net (code "77") (name "unconnected-(IC1-~{CTS}-Pad11)") (class "Default")
      (node (ref "IC1") (pin "11") (pinfunction "~{CTS}_11") (pintype "input"))
    )
    (net (code "78") (name "unconnected-(IC1-~{DCD}-Pad10)") (class "Default")
      (node (ref "IC1") (pin "10") (pinfunction "~{DCD}_10") (pintype "input"))
    )
    (net (code "79") (name "unconnected-(IC1-~{DSR}-Pad9)") (class "Default")
      (node (ref "IC1") (pin "9") (pinfunction "~{DSR}_9") (pintype "input"))
    )
    (net (code "80") (name "unconnected-(IC1-~{DTR}-Pad2)") (class "Default")
      (node (ref "IC1") (pin "2") (pinfunction "~{DTR}_2") (pintype "output"))
    )
    (net (code "81") (name "unconnected-(IC1-~{RESET}-Pad19)") (class "Default")
      (node (ref "IC1") (pin "19") (pinfunction "~{RESET}_19") (pintype "input"))
    )
    (net (code "82") (name "unconnected-(IC1-~{RI}-Pad6)") (class "Default")
      (node (ref "IC1") (pin "6") (pinfunction "~{RI}_6") (pintype "input"))
    )
    (net (code "83") (name "unconnected-(IC1-~{RTS}-Pad3)") (class "Default")
      (node (ref "IC1") (pin "3") (pinfunction "~{RTS}_3") (pintype "output"))
    )
    (net (code "84") (name "unconnected-(U$6-A0_C0-Pad23)") (class "Default")
      (node (ref "U$6") (pin "23") (pinfunction "A0_C0_23") (pintype "bidirectional"))
    )
    (net (code "85") (name "unconnected-(U$6-A3_C3-Pad26)") (class "Default")
      (node (ref "U$6") (pin "26") (pinfunction "A3_C3_26") (pintype "bidirectional"))
    )
    (net (code "86") (name "unconnected-(U$6-A4_C4_SDA-Pad27)") (class "Default")
      (node (ref "U$6") (pin "27") (pinfunction "A4_C4_SDA_27") (pintype "bidirectional"))
    )
    (net (code "87") (name "unconnected-(U$6-A5_C5_SCL-Pad28)") (class "Default")
      (node (ref "U$6") (pin "28") (pinfunction "A5_C5_SCL_28") (pintype "bidirectional"))
    )
    (net (code "88") (name "unconnected-(U$6-A6-Pad19)") (class "Default")
      (node (ref "U$6") (pin "19") (pinfunction "A6_19") (pintype "bidirectional"))
    )
    (net (code "89") (name "unconnected-(U$6-A7-Pad22)") (class "Default")
      (node (ref "U$6") (pin "22") (pinfunction "A7_22") (pintype "bidirectional"))
    )
    (net (code "90") (name "unconnected-(U$6-B0-Pad12)") (class "Default")
      (node (ref "U$6") (pin "12") (pinfunction "B0_12") (pintype "bidirectional"))
    )
    (net (code "91") (name "unconnected-(U$6-B1_PWM-Pad13)") (class "Default")
      (node (ref "U$6") (pin "13") (pinfunction "B1_PWM_13") (pintype "bidirectional"))
    )
    (net (code "92") (name "unconnected-(U$6-B2-Pad14)") (class "Default")
      (node (ref "U$6") (pin "14") (pinfunction "B2_14") (pintype "bidirectional"))
    )
    (net (code "93") (name "unconnected-(U$6-D3_PWM-Pad1)") (class "Default")
      (node (ref "U$6") (pin "1") (pinfunction "D3_PWM_1") (pintype "bidirectional"))
    )
    (net (code "94") (name "unconnected-(U$6-D4-Pad2)") (class "Default")
      (node (ref "U$6") (pin "2") (pinfunction "D4_2") (pintype "bidirectional"))
    )
    (net (code "95") (name "unconnected-(U$6-D5_PWM-Pad9)") (class "Default")
      (node (ref "U$6") (pin "9") (pinfunction "D5_PWM_9") (pintype "bidirectional"))
    )
    (net (code "96") (name "unconnected-(U$6-D7-Pad11)") (class "Default")
      (node (ref "U$6") (pin "11") (pinfunction "D7_11") (pintype "bidirectional"))
    )
    (net (code "97") (name "unconnected-(U$6-GND2-Pad5)") (class "Default")
      (node (ref "U$6") (pin "5") (pinfunction "GND2_5") (pintype "bidirectional"))
    )
    (net (code "98") (name "unconnected-(U$6-GND3-Pad21)") (class "Default")
      (node (ref "U$6") (pin "21") (pinfunction "GND3_21") (pintype "bidirectional"))
    )
    (net (code "99") (name "unconnected-(U$6-RESET-Pad29)") (class "Default")
      (node (ref "U$6") (pin "29") (pinfunction "RESET_29") (pintype "bidirectional"))
    )
    (net (code "100") (name "unconnected-(U$33-Pad2)") (class "Default")
      (node (ref "U$33") (pin "2") (pinfunction "2_2") (pintype "bidirectional"))
    )
    (net (code "101") (name "unconnected-(U$47-PadL)") (class "Default")
      (node (ref "U$47") (pin "L") (pinfunction "L_L") (pintype "bidirectional"))
    )
    (net (code "102") (name "unconnected-(U$48-PadD)") (class "Default")
      (node (ref "U$48") (pin "D") (pinfunction "D_D") (pintype "bidirectional"))
    )
    (net (code "103") (name "unconnected-(U1-LOADMOD-Pad2)") (class "Default")
      (node (ref "U1") (pin "2") (pinfunction "LOADMOD_2") (pintype "bidirectional"))
    )
    (net (code "104") (name "unconnected-(U1-NC1-Pad20)") (class "Default")
      (node (ref "U1") (pin "20") (pinfunction "NC1_20") (pintype "bidirectional"))
    )
    (net (code "105") (name "unconnected-(U1-NC2-Pad21)") (class "Default")
      (node (ref "U1") (pin "21") (pinfunction "NC2_21") (pintype "bidirectional"))
    )
    (net (code "106") (name "unconnected-(U1-NC3-Pad22)") (class "Default")
      (node (ref "U1") (pin "22") (pinfunction "NC3_22") (pintype "bidirectional"))
    )
    (net (code "107") (name "unconnected-(U3-USBID-PadID1)") (class "Default")
      (node (ref "U3") (pin "ID1") (pinfunction "USBID_ID1") (pintype "bidirectional"))
    )
    (net (code "108") (name "unconnected-(U4-GPIO5-PadGPOIO5)") (class "Default")
      (node (ref "U4") (pin "GPOIO5") (pinfunction "GPIO5_GPOIO5") (pintype "bidirectional"))
    )
    (net (code "109") (name "unconnected-(U4-PadEXT_RSTB)") (class "Default")
      (node (ref "U4") (pin "EXT_RSTB") (pinfunction "EXT_RSTB_EXT_RSTB") (pintype "bidirectional"))
    )
    (net (code "110") (name "unconnected-(U4-PadGPIO4)") (class "Default")
      (node (ref "U4") (pin "GPIO4") (pinfunction "GPIO4_GPIO4") (pintype "bidirectional"))
    )
    (net (code "111") (name "unconnected-(U4-PadMTCK)") (class "Default")
      (node (ref "U4") (pin "MTCK") (pinfunction "MTCK_MTCK") (pintype "bidirectional"))
    )
    (net (code "112") (name "unconnected-(U4-PadMTDI)") (class "Default")
      (node (ref "U4") (pin "MTDI") (pinfunction "MTDI_MTDI") (pintype "bidirectional"))
    )
    (net (code "113") (name "unconnected-(U4-PadMTDO)") (class "Default")
      (node (ref "U4") (pin "MTDO") (pinfunction "MTDO_MTDO") (pintype "bidirectional"))
    )
    (net (code "114") (name "unconnected-(U4-PadMTMS)") (class "Default")
      (node (ref "U4") (pin "MTMS") (pinfunction "MTMS_MTMS") (pintype "bidirectional"))
    )
    (net (code "115") (name "unconnected-(U4-PadTOUT)") (class "Default")
      (node (ref "U4") (pin "TOUT") (pinfunction "TOUT_TOUT") (pintype "bidirectional"))
    )
    (net (code "116") (name "unconnected-(U4-PadXPD_DCDC)") (class "Default")
      (node (ref "U4") (pin "XPD_DCDC") (pinfunction "XPD_DCDC_XPD_DCDC") (pintype "bidirectional"))
    )
  )
)
